# Display.net
KiCad netlist of a schematic drawn in Altium Designer
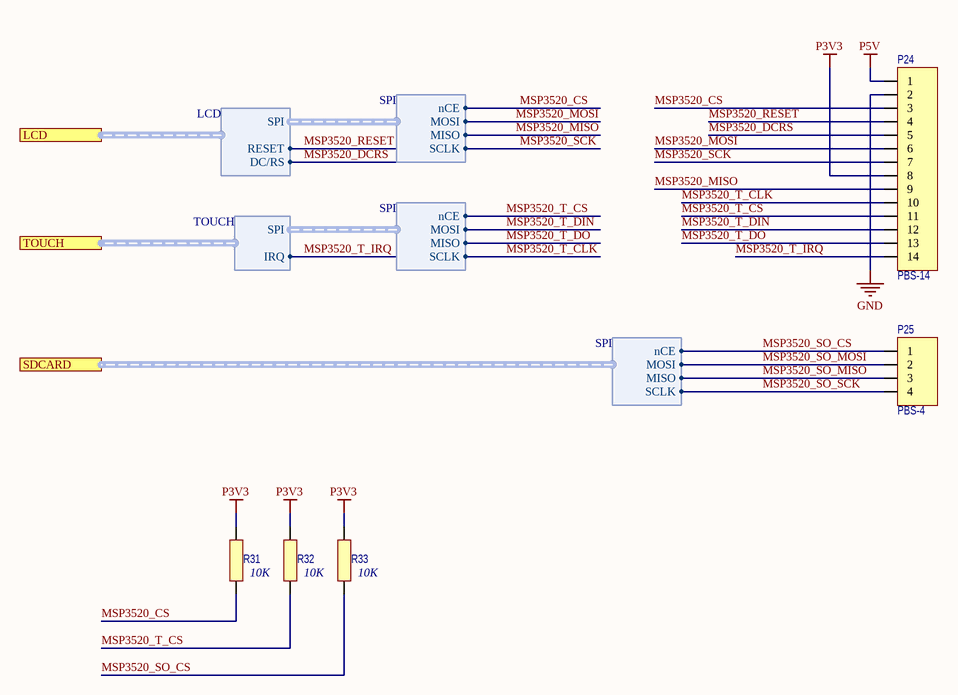
[diagram p0: Display.SchDoc]

(export (version "E")
  (design (tool "Eeschema 10.0.6"))
  (components
    (comp (ref "P24") (value "PBS-14") (footprint "PBS-14") (libsource (lib "my_AP_lib_sch") (part "PBS-14")))
    (comp (ref "P25") (value "PBS-4") (footprint "PBS-4") (libsource (lib "my_AP_lib_sch") (part "PBS-4")))
    (comp (ref "R31")
      (value "10K")
      (footprint "R0805")
      (fields (field (name "Comment") "R0805"))
      (libsource (lib "my_AP_lib_sch") (part "R0805"))
    )
    (comp (ref "R32")
      (value "10K")
      (footprint "R0805")
      (fields (field (name "Comment") "R0805"))
      (libsource (lib "my_AP_lib_sch") (part "R0805"))
    )
    (comp (ref "R33")
      (value "10K")
      (footprint "R0805")
      (fields (field (name "Comment") "R0805"))
      (libsource (lib "my_AP_lib_sch") (part "R0805"))
    )
  )
  (nets
    (net (code "5") (name "/MSP3520_CS") (class "Default")
      (node (ref "P24") (pin "3") (pinfunction "3_3") (pintype "passive"))
      (node (ref "R31") (pin "1") (pinfunction "1_1") (pintype "passive"))
    )
    (net (code "6") (name "/MSP3520_DCRS") (class "Default")
      (node (ref "P24") (pin "5") (pinfunction "5_5") (pintype "passive"))
    )
    (net (code "7") (name "/MSP3520_MISO") (class "Default")
      (node (ref "P24") (pin "9") (pinfunction "9_9") (pintype "passive"))
    )
    (net (code "8") (name "/MSP3520_MOSI") (class "Default")
      (node (ref "P24") (pin "6") (pinfunction "6_6") (pintype "passive"))
    )
    (net (code "9") (name "/MSP3520_RESET") (class "Default")
      (node (ref "P24") (pin "4") (pinfunction "4_4") (pintype "passive"))
    )
    (net (code "10") (name "/MSP3520_SCK") (class "Default")
      (node (ref "P24") (pin "7") (pinfunction "7_7") (pintype "passive"))
    )
    (net (code "11") (name "/MSP3520_SO_CS") (class "Default")
      (node (ref "P25") (pin "1") (pinfunction "1_1") (pintype "passive"))
      (node (ref "R33") (pin "1") (pinfunction "1_1") (pintype "passive"))
    )
    (net (code "12") (name "/MSP3520_SO_MISO") (class "Default")
      (node (ref "P25") (pin "3") (pinfunction "3_3") (pintype "passive"))
    )
    (net (code "13") (name "/MSP3520_SO_MOSI") (class "Default")
      (node (ref "P25") (pin "2") (pinfunction "2_2") (pintype "passive"))
    )
    (net (code "14") (name "/MSP3520_SO_SCK") (class "Default")
      (node (ref "P25") (pin "4") (pinfunction "4_4") (pintype "passive"))
    )
    (net (code "15") (name "/MSP3520_T_CLK") (class "Default")
      (node (ref "P24") (pin "10") (pinfunction "10_10") (pintype "passive"))
    )
    (net (code "16") (name "/MSP3520_T_CS") (class "Default")
      (node (ref "P24") (pin "11") (pinfunction "11_11") (pintype "passive"))
      (node (ref "R32") (pin "1") (pinfunction "1_1") (pintype "passive"))
    )
    (net (code "17") (name "/MSP3520_T_DIN") (class "Default")
      (node (ref "P24") (pin "12") (pinfunction "12_12") (pintype "passive"))
    )
    (net (code "18") (name "/MSP3520_T_DO") (class "Default")
      (node (ref "P24") (pin "13") (pinfunction "13_13") (pintype "passive"))
    )
    (net (code "19") (name "/MSP3520_T_IRQ") (class "Default")
      (node (ref "P24") (pin "14") (pinfunction "14_14") (pintype "passive"))
    )
    (net (code "22") (name "GND") (class "Default")
      (node (ref "P24") (pin "2") (pinfunction "2_2") (pintype "passive"))
    )
    (net (code "23") (name "P3V3") (class "Default")
      (node (ref "P24") (pin "8") (pinfunction "8_8") (pintype "passive"))
      (node (ref "R31") (pin "2") (pinfunction "2_2") (pintype "passive"))
      (node (ref "R32") (pin "2") (pinfunction "2_2") (pintype "passive"))
      (node (ref "R33") (pin "2") (pinfunction "2_2") (pintype "passive"))
    )
    (net (code "24") (name "P5V") (class "Default")
      (node (ref "P24") (pin "1") (pinfunction "1_1") (pintype "passive"))
    )
  )
)
